# 9_-STM32F407_Controller.net
KiCad netlist of a schematic drawn in Altium Designer
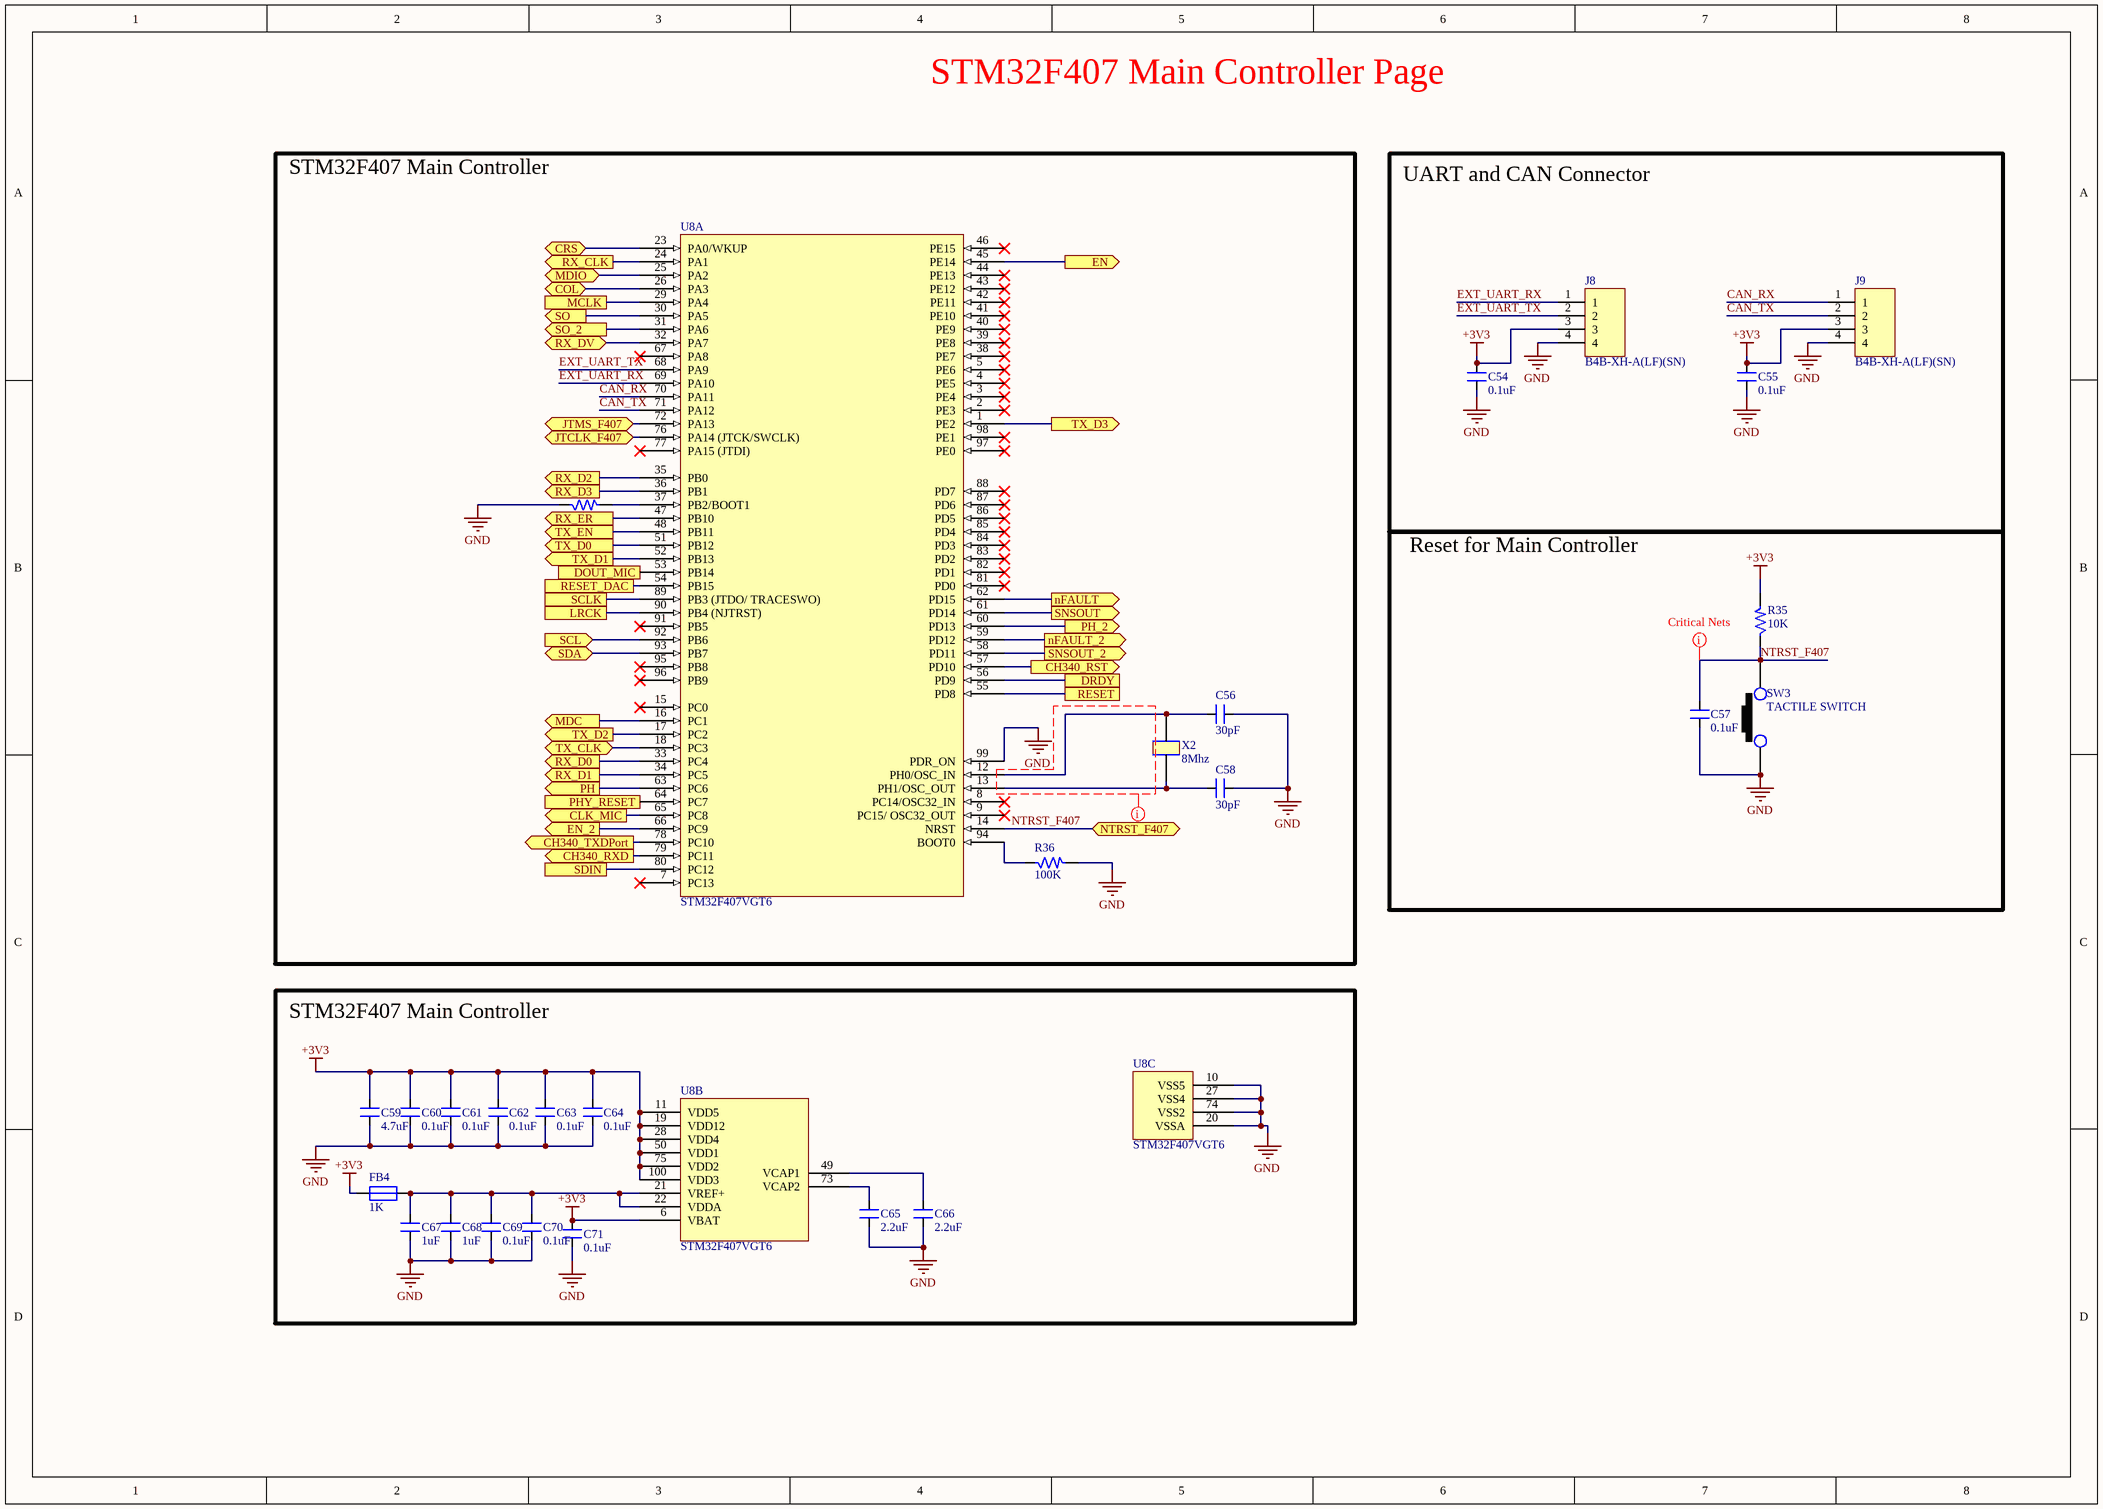
[diagram p0: [9]-STM32F407 Controller.SchDoc]

(export (version "E")
  (design (tool "Eeschema 10.0.6"))
  (components
    (comp (ref "C54")
      (value "0.1uF")
      (footprint "CAP_0805")
      (description "0.1µF ±10% 50V Ceramic Capacitor X7R 0805 (2012 Metric)")
      (fields
        (field (name "MANUFACTURER") "Samsung")
        (field (name "MANUFACTURER PART NUMBER") "CL21B104KBCNNNC")
      )
      (libsource (lib "ESTEEMPCBLIB") (part "CAP_0.1uF-50V-10%-0805"))
    )
    (comp (ref "C55")
      (value "0.1uF")
      (footprint "CAP_0805")
      (description "0.1µF ±10% 50V Ceramic Capacitor X7R 0805 (2012 Metric)")
      (fields
        (field (name "MANUFACTURER") "Samsung")
        (field (name "MANUFACTURER PART NUMBER") "CL21B104KBCNNNC")
      )
      (libsource (lib "ESTEEMPCBLIB") (part "CAP_0.1uF-50V-10%-0805"))
    )
    (comp (ref "C56")
      (value "30pF")
      (footprint "CAP_0805")
      (description "±10% 50V Ceramic Capacitor C0G, NP0 0805 (2012 Metric)")
      (fields
        (field (name "MANUFACTURER PART NUMBER") "C0805C300K5GAC7800")
        (field (name "MANUFACTURER") "KEMET")
      )
      (libsource (lib "ESTEEMPCBLIB") (part "CAP_30pF-50V-10%-0805"))
    )
    (comp (ref "C57")
      (value "0.1uF")
      (footprint "CAP_0805")
      (description "0.1µF ±10% 50V Ceramic Capacitor X7R 0805 (2012 Metric)")
      (fields
        (field (name "MANUFACTURER") "Samsung")
        (field (name "MANUFACTURER PART NUMBER") "CL21B104KBCNNNC")
      )
      (libsource (lib "ESTEEMPCBLIB") (part "CAP_0.1uF-50V-10%-0805"))
    )
    (comp (ref "C58")
      (value "30pF")
      (footprint "CAP_0805")
      (description "±10% 50V Ceramic Capacitor C0G, NP0 0805 (2012 Metric)")
      (fields
        (field (name "MANUFACTURER PART NUMBER") "C0805C300K5GAC7800")
        (field (name "MANUFACTURER") "KEMET")
      )
      (libsource (lib "ESTEEMPCBLIB") (part "CAP_30pF-50V-10%-0805"))
    )
    (comp (ref "C59")
      (value "4.7uF")
      (footprint "CAP_0805")
      (description "4.7µF ±10% 50V Ceramic Capacitor X5R 0805 (2012 Metric)")
      (fields
        (field (name "MANUFACTURER") "Yageo")
        (field (name "MANUFACTURER PART NUMBER") "GRM21BR61H475KE51L")
      )
      (libsource (lib "ESTEEMPCBLIB") (part "CAP_4.7uF-50V-10%-0805"))
    )
    (comp (ref "C60")
      (value "0.1uF")
      (footprint "CAP_0805")
      (description "0.1µF ±10% 50V Ceramic Capacitor X7R 0805 (2012 Metric)")
      (fields
        (field (name "MANUFACTURER") "Samsung")
        (field (name "MANUFACTURER PART NUMBER") "CL21B104KBCNNNC")
      )
      (libsource (lib "ESTEEMPCBLIB") (part "CAP_0.1uF-50V-10%-0805"))
    )
    (comp (ref "C61")
      (value "0.1uF")
      (footprint "CAP_0805")
      (description "0.1µF ±10% 50V Ceramic Capacitor X7R 0805 (2012 Metric)")
      (fields
        (field (name "MANUFACTURER") "Samsung")
        (field (name "MANUFACTURER PART NUMBER") "CL21B104KBCNNNC")
      )
      (libsource (lib "ESTEEMPCBLIB") (part "CAP_0.1uF-50V-10%-0805"))
    )
    (comp (ref "C62")
      (value "0.1uF")
      (footprint "CAP_0805")
      (description "0.1µF ±10% 50V Ceramic Capacitor X7R 0805 (2012 Metric)")
      (fields
        (field (name "MANUFACTURER") "Samsung")
        (field (name "MANUFACTURER PART NUMBER") "CL21B104KBCNNNC")
      )
      (libsource (lib "ESTEEMPCBLIB") (part "CAP_0.1uF-50V-10%-0805"))
    )
    (comp (ref "C63")
      (value "0.1uF")
      (footprint "CAP_0805")
      (description "0.1µF ±10% 50V Ceramic Capacitor X7R 0805 (2012 Metric)")
      (fields
        (field (name "MANUFACTURER") "Samsung")
        (field (name "MANUFACTURER PART NUMBER") "CL21B104KBCNNNC")
      )
      (libsource (lib "ESTEEMPCBLIB") (part "CAP_0.1uF-50V-10%-0805"))
    )
    (comp (ref "C64")
      (value "0.1uF")
      (footprint "CAP_0805")
      (description "0.1µF ±10% 50V Ceramic Capacitor X7R 0805 (2012 Metric)")
      (fields
        (field (name "MANUFACTURER") "Samsung")
        (field (name "MANUFACTURER PART NUMBER") "CL21B104KBCNNNC")
      )
      (libsource (lib "ESTEEMPCBLIB") (part "CAP_0.1uF-50V-10%-0805"))
    )
    (comp (ref "C65")
      (value "2.2uF")
      (footprint "CAP_0805")
      (description "2.2µF ±10% 25V Ceramic Capacitor X7R 0805 (2012 Metric)")
      (fields
        (field (name "MANUFACTURER") "KEMET")
        (field (name "MANUFACTURER PART NUMBER") "CL21B225KAFNFNE")
      )
      (libsource (lib "ESTEEMPCBLIB") (part "CAP_2.2uF-25V-10%-0805"))
    )
    (comp (ref "C66")
      (value "2.2uF")
      (footprint "CAP_0805")
      (description "2.2µF ±10% 25V Ceramic Capacitor X7R 0805 (2012 Metric)")
      (fields
        (field (name "MANUFACTURER") "KEMET")
        (field (name "MANUFACTURER PART NUMBER") "CL21B225KAFNFNE")
      )
      (libsource (lib "ESTEEMPCBLIB") (part "CAP_2.2uF-25V-10%-0805"))
    )
    (comp (ref "C67")
      (value "1uF")
      (footprint "CAP_0805")
      (description "1µF ±5% 50V Ceramic Capacitor X7R 0805 (2012 Metric)")
      (fields
        (field (name "MANUFACTURER") "Samsung")
        (field (name "MANUFACTURER PART NUMBER") "CC0805JKX7R9BB105")
      )
      (libsource (lib "ESTEEMPCBLIB") (part "CAP_1uF-50V-5%-0805"))
    )
    (comp (ref "C68")
      (value "1uF")
      (footprint "CAP_0805")
      (description "1µF ±5% 50V Ceramic Capacitor X7R 0805 (2012 Metric)")
      (fields
        (field (name "MANUFACTURER") "Samsung")
        (field (name "MANUFACTURER PART NUMBER") "CC0805JKX7R9BB105")
      )
      (libsource (lib "ESTEEMPCBLIB") (part "CAP_1uF-50V-5%-0805"))
    )
    (comp (ref "C69")
      (value "0.1uF")
      (footprint "CAP_0805")
      (description "0.1µF ±10% 50V Ceramic Capacitor X7R 0805 (2012 Metric)")
      (fields
        (field (name "MANUFACTURER") "Samsung")
        (field (name "MANUFACTURER PART NUMBER") "CL21B104KBCNNNC")
      )
      (libsource (lib "ESTEEMPCBLIB") (part "CAP_0.1uF-50V-10%-0805"))
    )
    (comp (ref "C70")
      (value "0.1uF")
      (footprint "CAP_0805")
      (description "0.1µF ±10% 50V Ceramic Capacitor X7R 0805 (2012 Metric)")
      (fields
        (field (name "MANUFACTURER") "Samsung")
        (field (name "MANUFACTURER PART NUMBER") "CL21B104KBCNNNC")
      )
      (libsource (lib "ESTEEMPCBLIB") (part "CAP_0.1uF-50V-10%-0805"))
    )
    (comp (ref "C71")
      (value "0.1uF")
      (footprint "CAP_0805")
      (description "0.1µF ±10% 50V Ceramic Capacitor X7R 0805 (2012 Metric)")
      (fields
        (field (name "MANUFACTURER") "Samsung")
        (field (name "MANUFACTURER PART NUMBER") "CL21B104KBCNNNC")
      )
      (libsource (lib "ESTEEMPCBLIB") (part "CAP_0.1uF-50V-10%-0805"))
    )
    (comp (ref "FB4")
      (value "1K")
      (footprint "IND_0805")
      (description "1 kOhms @ 100MHz 1 Power Line Ferrite Bead 0805 (2012 Metric) 1.6A")
      (fields
        (field (name "MANUFACTURER") "Laird")
        (field (name "MANUFACTURER PART NUMBER") "BLM21SP102SH1D")
      )
      (libsource (lib "ESTEEMPCBLIB") (part "FB_1K-100MHZ-1.6A-0805"))
    )
    (comp (ref "J8")
      (value "B4B-XH-A(LF)(SN)")
      (footprint "CON4_100_B4B-XH-A_TH_ST")
      (description "4 Pins, 1 Row 2.54mm Pitch, straight Connector, male")
      (fields (field (name "MANUFACTURER") "Wurth Electronics") (field (name "MATING PART NUMBER") "XHP-4"))
      (libsource (lib "ESTEEMPCBLIB") (part "CON-PLG_4X1-100-ST-TH"))
    )
    (comp (ref "J9")
      (value "B4B-XH-A(LF)(SN)")
      (footprint "CON4_100_B4B-XH-A_TH_ST")
      (description "4 Pins, 1 Row 2.54mm Pitch, straight Connector, male")
      (fields (field (name "MANUFACTURER") "Wurth Electronics") (field (name "MATING PART NUMBER") "XHP-4"))
      (libsource (lib "ESTEEMPCBLIB") (part "CON-PLG_4X1-100-ST-TH"))
    )
    (comp (ref "R34")
      (value "100K")
      (footprint "RES_0603")
      (description "100 kOhms ±1% 0.1W, 1/10W Chip Resistor 0603 (1608 Metric) Automotive AEC-Q200 Thick Film")
      (fields
        (field (name "MANUFACTURER") "Stackpole Electronics")
        (field (name "MANUFACTURER PART NUMBER") "RMCF0603FT100K")
      )
      (libsource (lib "ESTEEMPCBLIB") (part "RES_100K-0.1W-1%-0603"))
    )
    (comp (ref "R35")
      (value "10K")
      (footprint "RES_0603")
      (description "10 kOhms ±1% 0.1W, 1/10W Chip Resistor 0603 (1608 Metric) Automotive AEC-Q200 Thick Film")
      (fields (field (name "MANUFACTURER") "Walsin") (field (name "MANUFACTURER PART NUMBER") "WR06X1002FTL"))
      (libsource (lib "ESTEEMPCBLIB") (part "RES_10K-0.1W-1%-0603"))
    )
    (comp (ref "R36")
      (value "100K")
      (footprint "RES_0603")
      (description "100 kOhms ±1% 0.1W, 1/10W Chip Resistor 0603 (1608 Metric) Automotive AEC-Q200 Thick Film")
      (fields
        (field (name "MANUFACTURER") "Stackpole Electronics")
        (field (name "MANUFACTURER PART NUMBER") "RMCF0603FT100K")
      )
      (libsource (lib "ESTEEMPCBLIB") (part "RES_100K-0.1W-1%-0603"))
    )
    (comp (ref "SW3")
      (value "TACTILE SWITCH")
      (footprint "SW_342_SMD")
      (description "Tactile Switch SPST-NO Top Actuated Surface Mount")
      (fields
        (field (name "MANUFACTURER") "ITT C&K")
        (field (name "MANUFACTURER PART NUMBER") "RS-282G05A3-SMRT")
      )
      (libsource (lib "ESTEEMPCBLIB") (part "SW1_RS-282G05A3-SMRT-SMD"))
    )
    (comp (ref "U8")
      (value "STM32F407VGT6")
      (footprint "QFN100_19.6_669_58X10_SMD")
      (description "ARM® Cortex®-M4 STM32F4 Microcontroller IC 32-Bit 168MHz 1MB (1M x 8) FLASH 100-LQFP (14x14)")
      (fields (field (name "MANUFACTURER") "STMicroelectronics"))
      (libsource (lib "ESTEEMPCBLIB") (part "IC_STM32F407VGT6"))
    )
    (comp (ref "X2")
      (value "8Mhz")
      (footprint "XTAL_314_240X47_SMD")
      (description "8MHz ±30ppm Crystal 32pF 60 Ohms HC-49/US")
      (fields
        (field (name "MANUFACTURER") "Fox Electronics")
        (field (name "MANUFACTURER PART NUMBER") "ECS-80-32-5PX-TR")
      )
      (libsource (lib "ESTEEMPCBLIB") (part "XTAL_8MHZ-ECS-80-32-5PX-SMD"))
    )
  )
  (nets
    (net (code "1") (name "+3V3") (class "Default")
      (node (ref "C54") (pin "2") (pinfunction "2_2") (pintype "passive"))
      (node (ref "C55") (pin "2") (pinfunction "2_2") (pintype "passive"))
      (node (ref "C59") (pin "2") (pinfunction "2_2") (pintype "passive"))
      (node (ref "C60") (pin "2") (pinfunction "2_2") (pintype "passive"))
      (node (ref "C61") (pin "2") (pinfunction "2_2") (pintype "passive"))
      (node (ref "C62") (pin "2") (pinfunction "2_2") (pintype "passive"))
      (node (ref "C63") (pin "2") (pinfunction "2_2") (pintype "passive"))
      (node (ref "C64") (pin "2") (pinfunction "2_2") (pintype "passive"))
      (node (ref "C71") (pin "2") (pinfunction "2_2") (pintype "passive"))
      (node (ref "FB4") (pin "1") (pinfunction "1_1") (pintype "passive"))
      (node (ref "J8") (pin "3") (pinfunction "3_3") (pintype "passive"))
      (node (ref "J9") (pin "3") (pinfunction "3_3") (pintype "passive"))
      (node (ref "R35") (pin "2") (pinfunction "2_2") (pintype "passive"))
      (node (ref "U8") (pin "100") (pinfunction "VDD3_100") (pintype "passive"))
      (node (ref "U8") (pin "11") (pinfunction "VDD5_11") (pintype "passive"))
      (node (ref "U8") (pin "19") (pinfunction "VDD12_19") (pintype "passive"))
      (node (ref "U8") (pin "28") (pinfunction "VDD4_28") (pintype "passive"))
      (node (ref "U8") (pin "50") (pinfunction "VDD1_50") (pintype "passive"))
      (node (ref "U8") (pin "6") (pinfunction "VBAT_6") (pintype "passive"))
      (node (ref "U8") (pin "75") (pinfunction "VDD2_75") (pintype "passive"))
    )
    (net (code "2") (name "/CAN_RX") (class "Default")
      (node (ref "J9") (pin "1") (pinfunction "1_1") (pintype "passive"))
      (node (ref "U8") (pin "70") (pinfunction "PA11_70") (pintype "input"))
    )
    (net (code "3") (name "/CAN_TX") (class "Default")
      (node (ref "J9") (pin "2") (pinfunction "2_2") (pintype "passive"))
      (node (ref "U8") (pin "71") (pinfunction "PA12_71") (pintype "input"))
    )
    (net (code "4") (name "/CH340_RST") (class "Default")
      (node (ref "U8") (pin "57") (pinfunction "PD10_57") (pintype "input"))
    )
    (net (code "5") (name "/CH340_RXD") (class "Default")
      (node (ref "U8") (pin "79") (pinfunction "PC11_79") (pintype "input"))
    )
    (net (code "6") (name "/CH340_TXDPort") (class "Default")
      (node (ref "U8") (pin "78") (pinfunction "PC10_78") (pintype "input"))
    )
    (net (code "7") (name "/CLK_MIC") (class "Default")
      (node (ref "U8") (pin "65") (pinfunction "PC8_65") (pintype "input"))
    )
    (net (code "8") (name "/COL") (class "Default")
      (node (ref "U8") (pin "26") (pinfunction "PA3_26") (pintype "input"))
    )
    (net (code "9") (name "/CRS") (class "Default")
      (node (ref "U8") (pin "23") (pinfunction "PA0/WKUP_23") (pintype "input"))
    )
    (net (code "10") (name "/DOUT_MIC") (class "Default")
      (node (ref "U8") (pin "53") (pinfunction "PB14_53") (pintype "input"))
    )
    (net (code "11") (name "/DRDY") (class "Default")
      (node (ref "U8") (pin "56") (pinfunction "PD9_56") (pintype "input"))
    )
    (net (code "12") (name "/EN") (class "Default")
      (node (ref "U8") (pin "45") (pinfunction "PE14_45") (pintype "input"))
    )
    (net (code "13") (name "/EN_2") (class "Default")
      (node (ref "U8") (pin "66") (pinfunction "PC9_66") (pintype "input"))
    )
    (net (code "14") (name "/EXT_UART_RX") (class "Default")
      (node (ref "J8") (pin "1") (pinfunction "1_1") (pintype "passive"))
      (node (ref "U8") (pin "69") (pinfunction "PA10_69") (pintype "input"))
    )
    (net (code "15") (name "/EXT_UART_TX") (class "Default")
      (node (ref "J8") (pin "2") (pinfunction "2_2") (pintype "passive"))
      (node (ref "U8") (pin "68") (pinfunction "PA9_68") (pintype "input"))
    )
    (net (code "16") (name "/JTCLK_F407") (class "Default")
      (node (ref "U8") (pin "76") (pinfunction "PA14_(JTCK/SWCLK)_76") (pintype "input"))
    )
    (net (code "17") (name "/JTMS_F407") (class "Default")
      (node (ref "U8") (pin "72") (pinfunction "PA13_72") (pintype "input"))
    )
    (net (code "18") (name "/LRCK") (class "Default")
      (node (ref "U8") (pin "90") (pinfunction "PB4_(NJTRST)_90") (pintype "input"))
    )
    (net (code "19") (name "/MCLK") (class "Default")
      (node (ref "U8") (pin "29") (pinfunction "PA4_29") (pintype "input"))
    )
    (net (code "20") (name "/MDC") (class "Default")
      (node (ref "U8") (pin "16") (pinfunction "PC1_16") (pintype "input"))
    )
    (net (code "21") (name "/MDIO") (class "Default")
      (node (ref "U8") (pin "25") (pinfunction "PA2_25") (pintype "input"))
    )
    (net (code "22") (name "/NTRST_F407") (class "Default")
      (node (ref "C57") (pin "2") (pinfunction "2_2") (pintype "passive"))
      (node (ref "R35") (pin "1") (pinfunction "1_1") (pintype "passive"))
      (node (ref "SW3") (pin "2") (pinfunction "2_2") (pintype "passive"))
      (node (ref "U8") (pin "14") (pinfunction "NRST_14") (pintype "input"))
    )
    (net (code "23") (name "/PH") (class "Default")
      (node (ref "U8") (pin "63") (pinfunction "PC6_63") (pintype "input"))
    )
    (net (code "24") (name "/PHY_RESET") (class "Default")
      (node (ref "U8") (pin "64") (pinfunction "PC7_64") (pintype "input"))
    )
    (net (code "25") (name "/PH_2") (class "Default")
      (node (ref "U8") (pin "60") (pinfunction "PD13_60") (pintype "input"))
    )
    (net (code "26") (name "/RESET") (class "Default")
      (node (ref "U8") (pin "55") (pinfunction "PD8_55") (pintype "input"))
    )
    (net (code "27") (name "/RESET_DAC") (class "Default")
      (node (ref "U8") (pin "54") (pinfunction "PB15_54") (pintype "input"))
    )
    (net (code "28") (name "/RX_CLK") (class "Default")
      (node (ref "U8") (pin "24") (pinfunction "PA1_24") (pintype "input"))
    )
    (net (code "29") (name "/RX_D0") (class "Default")
      (node (ref "U8") (pin "33") (pinfunction "PC4_33") (pintype "input"))
    )
    (net (code "30") (name "/RX_D1") (class "Default")
      (node (ref "U8") (pin "34") (pinfunction "PC5_34") (pintype "input"))
    )
    (net (code "31") (name "/RX_D2") (class "Default")
      (node (ref "U8") (pin "35") (pinfunction "PB0_35") (pintype "input"))
    )
    (net (code "32") (name "/RX_D3") (class "Default")
      (node (ref "U8") (pin "36") (pinfunction "PB1_36") (pintype "input"))
    )
    (net (code "33") (name "/RX_DV") (class "Default")
      (node (ref "U8") (pin "32") (pinfunction "PA7_32") (pintype "input"))
    )
    (net (code "34") (name "/RX_ER") (class "Default")
      (node (ref "U8") (pin "47") (pinfunction "PB10_47") (pintype "input"))
    )
    (net (code "35") (name "/SCL") (class "Default")
      (node (ref "U8") (pin "92") (pinfunction "PB6_92") (pintype "input"))
    )
    (net (code "36") (name "/SCLK") (class "Default")
      (node (ref "U8") (pin "89") (pinfunction "PB3_(JTDO/_TRACESWO)_89") (pintype "input"))
    )
    (net (code "37") (name "/SDA") (class "Default")
      (node (ref "U8") (pin "93") (pinfunction "PB7_93") (pintype "input"))
    )
    (net (code "38") (name "/SDIN") (class "Default")
      (node (ref "U8") (pin "80") (pinfunction "PC12_80") (pintype "input"))
    )
    (net (code "39") (name "/SNSOUT") (class "Default")
      (node (ref "U8") (pin "61") (pinfunction "PD14_61") (pintype "input"))
    )
    (net (code "40") (name "/SNSOUT_2") (class "Default")
      (node (ref "U8") (pin "58") (pinfunction "PD11_58") (pintype "input"))
    )
    (net (code "41") (name "/SO") (class "Default")
      (node (ref "U8") (pin "30") (pinfunction "PA5_30") (pintype "input"))
    )
    (net (code "42") (name "/SO_2") (class "Default")
      (node (ref "U8") (pin "31") (pinfunction "PA6_31") (pintype "input"))
    )
    (net (code "43") (name "/TX_CLK") (class "Default")
      (node (ref "U8") (pin "18") (pinfunction "PC3_18") (pintype "input"))
    )
    (net (code "44") (name "/TX_D0") (class "Default")
      (node (ref "U8") (pin "51") (pinfunction "PB12_51") (pintype "input"))
    )
    (net (code "45") (name "/TX_D1") (class "Default")
      (node (ref "U8") (pin "52") (pinfunction "PB13_52") (pintype "input"))
    )
    (net (code "46") (name "/TX_D2") (class "Default")
      (node (ref "U8") (pin "17") (pinfunction "PC2_17") (pintype "input"))
    )
    (net (code "47") (name "/TX_D3") (class "Default")
      (node (ref "U8") (pin "1") (pinfunction "PE2_1") (pintype "input"))
    )
    (net (code "48") (name "/TX_EN") (class "Default")
      (node (ref "U8") (pin "48") (pinfunction "PB11_48") (pintype "input"))
    )
    (net (code "49") (name "/nFAULT") (class "Default")
      (node (ref "U8") (pin "62") (pinfunction "PD15_62") (pintype "input"))
    )
    (net (code "50") (name "/nFAULT_2") (class "Default")
      (node (ref "U8") (pin "59") (pinfunction "PD12_59") (pintype "input"))
    )
    (net (code "51") (name "GND") (class "Default")
      (node (ref "C54") (pin "1") (pinfunction "1_1") (pintype "passive"))
      (node (ref "C55") (pin "1") (pinfunction "1_1") (pintype "passive"))
      (node (ref "C56") (pin "2") (pinfunction "2_2") (pintype "passive"))
      (node (ref "C57") (pin "1") (pinfunction "1_1") (pintype "passive"))
      (node (ref "C58") (pin "2") (pinfunction "2_2") (pintype "passive"))
      (node (ref "C59") (pin "1") (pinfunction "1_1") (pintype "passive"))
      (node (ref "C60") (pin "1") (pinfunction "1_1") (pintype "passive"))
      (node (ref "C61") (pin "1") (pinfunction "1_1") (pintype "passive"))
      (node (ref "C62") (pin "1") (pinfunction "1_1") (pintype "passive"))
      (node (ref "C63") (pin "1") (pinfunction "1_1") (pintype "passive"))
      (node (ref "C64") (pin "1") (pinfunction "1_1") (pintype "passive"))
      (node (ref "C65") (pin "1") (pinfunction "1_1") (pintype "passive"))
      (node (ref "C66") (pin "1") (pinfunction "1_1") (pintype "passive"))
      (node (ref "C67") (pin "1") (pinfunction "1_1") (pintype "passive"))
      (node (ref "C68") (pin "1") (pinfunction "1_1") (pintype "passive"))
      (node (ref "C69") (pin "1") (pinfunction "1_1") (pintype "passive"))
      (node (ref "C70") (pin "1") (pinfunction "1_1") (pintype "passive"))
      (node (ref "C71") (pin "1") (pinfunction "1_1") (pintype "passive"))
      (node (ref "J8") (pin "4") (pinfunction "4_4") (pintype "passive"))
      (node (ref "J9") (pin "4") (pinfunction "4_4") (pintype "passive"))
      (node (ref "R34") (pin "1") (pinfunction "1_1") (pintype "passive"))
      (node (ref "R36") (pin "2") (pinfunction "2_2") (pintype "passive"))
      (node (ref "SW3") (pin "1") (pinfunction "1_1") (pintype "passive"))
      (node (ref "U8") (pin "10") (pinfunction "VSS5_10") (pintype "passive"))
      (node (ref "U8") (pin "20") (pinfunction "VSSA_20") (pintype "passive"))
      (node (ref "U8") (pin "27") (pinfunction "VSS4_27") (pintype "passive"))
      (node (ref "U8") (pin "74") (pinfunction "VSS2_74") (pintype "passive"))
      (node (ref "U8") (pin "99") (pinfunction "PDR_ON_99") (pintype "input"))
    )
    (net (code "52") (name "Net-(U8A-BOOT0)") (class "Default")
      (node (ref "R36") (pin "1") (pinfunction "1_1") (pintype "passive"))
      (node (ref "U8") (pin "94") (pinfunction "BOOT0_94") (pintype "input"))
    )
    (net (code "53") (name "Net-(U8A-PB2{slash}BOOT1)") (class "Default")
      (node (ref "R34") (pin "2") (pinfunction "2_2") (pintype "passive"))
      (node (ref "U8") (pin "37") (pinfunction "PB2/BOOT1_37") (pintype "input"))
    )
    (net (code "54") (name "Net-(U8A-PH0{slash}OSC_IN)") (class "Default")
      (node (ref "C56") (pin "1") (pinfunction "1_1") (pintype "passive"))
      (node (ref "U8") (pin "12") (pinfunction "PH0/OSC_IN_12") (pintype "input"))
      (node (ref "X2") (pin "2") (pinfunction "2_2") (pintype "passive"))
    )
    (net (code "55") (name "Net-(U8A-PH1{slash}OSC_OUT)") (class "Default")
      (node (ref "C58") (pin "1") (pinfunction "1_1") (pintype "passive"))
      (node (ref "U8") (pin "13") (pinfunction "PH1/OSC_OUT_13") (pintype "input"))
      (node (ref "X2") (pin "1") (pinfunction "1_1") (pintype "passive"))
    )
    (net (code "56") (name "Net-(U8B-VCAP1)") (class "Default")
      (node (ref "C66") (pin "2") (pinfunction "2_2") (pintype "passive"))
      (node (ref "U8") (pin "49") (pinfunction "VCAP1_49") (pintype "passive"))
    )
    (net (code "57") (name "Net-(U8B-VCAP2)") (class "Default")
      (node (ref "C65") (pin "2") (pinfunction "2_2") (pintype "passive"))
      (node (ref "U8") (pin "73") (pinfunction "VCAP2_73") (pintype "passive"))
    )
    (net (code "58") (name "Net-(U8B-VDDA)") (class "Default")
      (node (ref "C67") (pin "2") (pinfunction "2_2") (pintype "passive"))
      (node (ref "C68") (pin "2") (pinfunction "2_2") (pintype "passive"))
      (node (ref "C69") (pin "2") (pinfunction "2_2") (pintype "passive"))
      (node (ref "C70") (pin "2") (pinfunction "2_2") (pintype "passive"))
      (node (ref "FB4") (pin "2") (pinfunction "2_2") (pintype "passive"))
      (node (ref "U8") (pin "21") (pinfunction "VREF+_21") (pintype "passive"))
      (node (ref "U8") (pin "22") (pinfunction "VDDA_22") (pintype "passive"))
    )
    (net (code "59") (name "unconnected-(U8A-PA8-Pad67)") (class "Default")
      (node (ref "U8") (pin "67") (pinfunction "PA8_67") (pintype "input+no_connect"))
    )
    (net (code "60") (name "unconnected-(U8A-PA15_(JTDI)-Pad77)") (class "Default")
      (node (ref "U8") (pin "77") (pinfunction "PA15_(JTDI)_77") (pintype "input+no_connect"))
    )
    (net (code "61") (name "unconnected-(U8A-PB5-Pad91)") (class "Default")
      (node (ref "U8") (pin "91") (pinfunction "PB5_91") (pintype "input+no_connect"))
    )
    (net (code "62") (name "unconnected-(U8A-PB8-Pad95)") (class "Default")
      (node (ref "U8") (pin "95") (pinfunction "PB8_95") (pintype "input+no_connect"))
    )
    (net (code "63") (name "unconnected-(U8A-PB9-Pad96)") (class "Default")
      (node (ref "U8") (pin "96") (pinfunction "PB9_96") (pintype "input+no_connect"))
    )
    (net (code "64") (name "unconnected-(U8A-PC0-Pad15)") (class "Default")
      (node (ref "U8") (pin "15") (pinfunction "PC0_15") (pintype "input+no_connect"))
    )
    (net (code "65") (name "unconnected-(U8A-PC13-Pad7)") (class "Default")
      (node (ref "U8") (pin "7") (pinfunction "PC13_7") (pintype "input+no_connect"))
    )
    (net (code "66") (name "unconnected-(U8A-PC14{slash}OSC32_IN-Pad8)") (class "Default")
      (node (ref "U8") (pin "8") (pinfunction "PC14/OSC32_IN_8") (pintype "input+no_connect"))
    )
    (net (code "67") (name "unconnected-(U8A-PC15{slash}_OSC32_OUT-Pad9)") (class "Default")
      (node (ref "U8") (pin "9") (pinfunction "PC15/_OSC32_OUT_9") (pintype "input+no_connect"))
    )
    (net (code "68") (name "unconnected-(U8A-PD0-Pad81)") (class "Default")
      (node (ref "U8") (pin "81") (pinfunction "PD0_81") (pintype "input+no_connect"))
    )
    (net (code "69") (name "unconnected-(U8A-PD1-Pad82)") (class "Default")
      (node (ref "U8") (pin "82") (pinfunction "PD1_82") (pintype "input+no_connect"))
    )
    (net (code "70") (name "unconnected-(U8A-PD2-Pad83)") (class "Default")
      (node (ref "U8") (pin "83") (pinfunction "PD2_83") (pintype "input+no_connect"))
    )
    (net (code "71") (name "unconnected-(U8A-PD3-Pad84)") (class "Default")
      (node (ref "U8") (pin "84") (pinfunction "PD3_84") (pintype "input+no_connect"))
    )
    (net (code "72") (name "unconnected-(U8A-PD4-Pad85)") (class "Default")
      (node (ref "U8") (pin "85") (pinfunction "PD4_85") (pintype "input+no_connect"))
    )
    (net (code "73") (name "unconnected-(U8A-PD5-Pad86)") (class "Default")
      (node (ref "U8") (pin "86") (pinfunction "PD5_86") (pintype "input+no_connect"))
    )
    (net (code "74") (name "unconnected-(U8A-PD6-Pad87)") (class "Default")
      (node (ref "U8") (pin "87") (pinfunction "PD6_87") (pintype "input+no_connect"))
    )
    (net (code "75") (name "unconnected-(U8A-PD7-Pad88)") (class "Default")
      (node (ref "U8") (pin "88") (pinfunction "PD7_88") (pintype "input+no_connect"))
    )
    (net (code "76") (name "unconnected-(U8A-PE0-Pad97)") (class "Default")
      (node (ref "U8") (pin "97") (pinfunction "PE0_97") (pintype "input+no_connect"))
    )
    (net (code "77") (name "unconnected-(U8A-PE1-Pad98)") (class "Default")
      (node (ref "U8") (pin "98") (pinfunction "PE1_98") (pintype "input+no_connect"))
    )
    (net (code "78") (name "unconnected-(U8A-PE3-Pad2)") (class "Default")
      (node (ref "U8") (pin "2") (pinfunction "PE3_2") (pintype "input+no_connect"))
    )
    (net (code "79") (name "unconnected-(U8A-PE4-Pad3)") (class "Default")
      (node (ref "U8") (pin "3") (pinfunction "PE4_3") (pintype "input+no_connect"))
    )
    (net (code "80") (name "unconnected-(U8A-PE5-Pad4)") (class "Default")
      (node (ref "U8") (pin "4") (pinfunction "PE5_4") (pintype "input+no_connect"))
    )
    (net (code "81") (name "unconnected-(U8A-PE6-Pad5)") (class "Default")
      (node (ref "U8") (pin "5") (pinfunction "PE6_5") (pintype "input+no_connect"))
    )
    (net (code "82") (name "unconnected-(U8A-PE7-Pad38)") (class "Default")
      (node (ref "U8") (pin "38") (pinfunction "PE7_38") (pintype "input+no_connect"))
    )
    (net (code "83") (name "unconnected-(U8A-PE8-Pad39)") (class "Default")
      (node (ref "U8") (pin "39") (pinfunction "PE8_39") (pintype "input+no_connect"))
    )
    (net (code "84") (name "unconnected-(U8A-PE9-Pad40)") (class "Default")
      (node (ref "U8") (pin "40") (pinfunction "PE9_40") (pintype "input+no_connect"))
    )
    (net (code "85") (name "unconnected-(U8A-PE10-Pad41)") (class "Default")
      (node (ref "U8") (pin "41") (pinfunction "PE10_41") (pintype "input+no_connect"))
    )
    (net (code "86") (name "unconnected-(U8A-PE11-Pad42)") (class "Default")
      (node (ref "U8") (pin "42") (pinfunction "PE11_42") (pintype "input+no_connect"))
    )
    (net (code "87") (name "unconnected-(U8A-PE12-Pad43)") (class "Default")
      (node (ref "U8") (pin "43") (pinfunction "PE12_43") (pintype "input+no_connect"))
    )
    (net (code "88") (name "unconnected-(U8A-PE13-Pad44)") (class "Default")
      (node (ref "U8") (pin "44") (pinfunction "PE13_44") (pintype "input+no_connect"))
    )
    (net (code "89") (name "unconnected-(U8A-PE15-Pad46)") (class "Default")
      (node (ref "U8") (pin "46") (pinfunction "PE15_46") (pintype "input+no_connect"))
    )
  )
)
